# Board.net
KiCad netlist of a schematic drawn in EAGLE
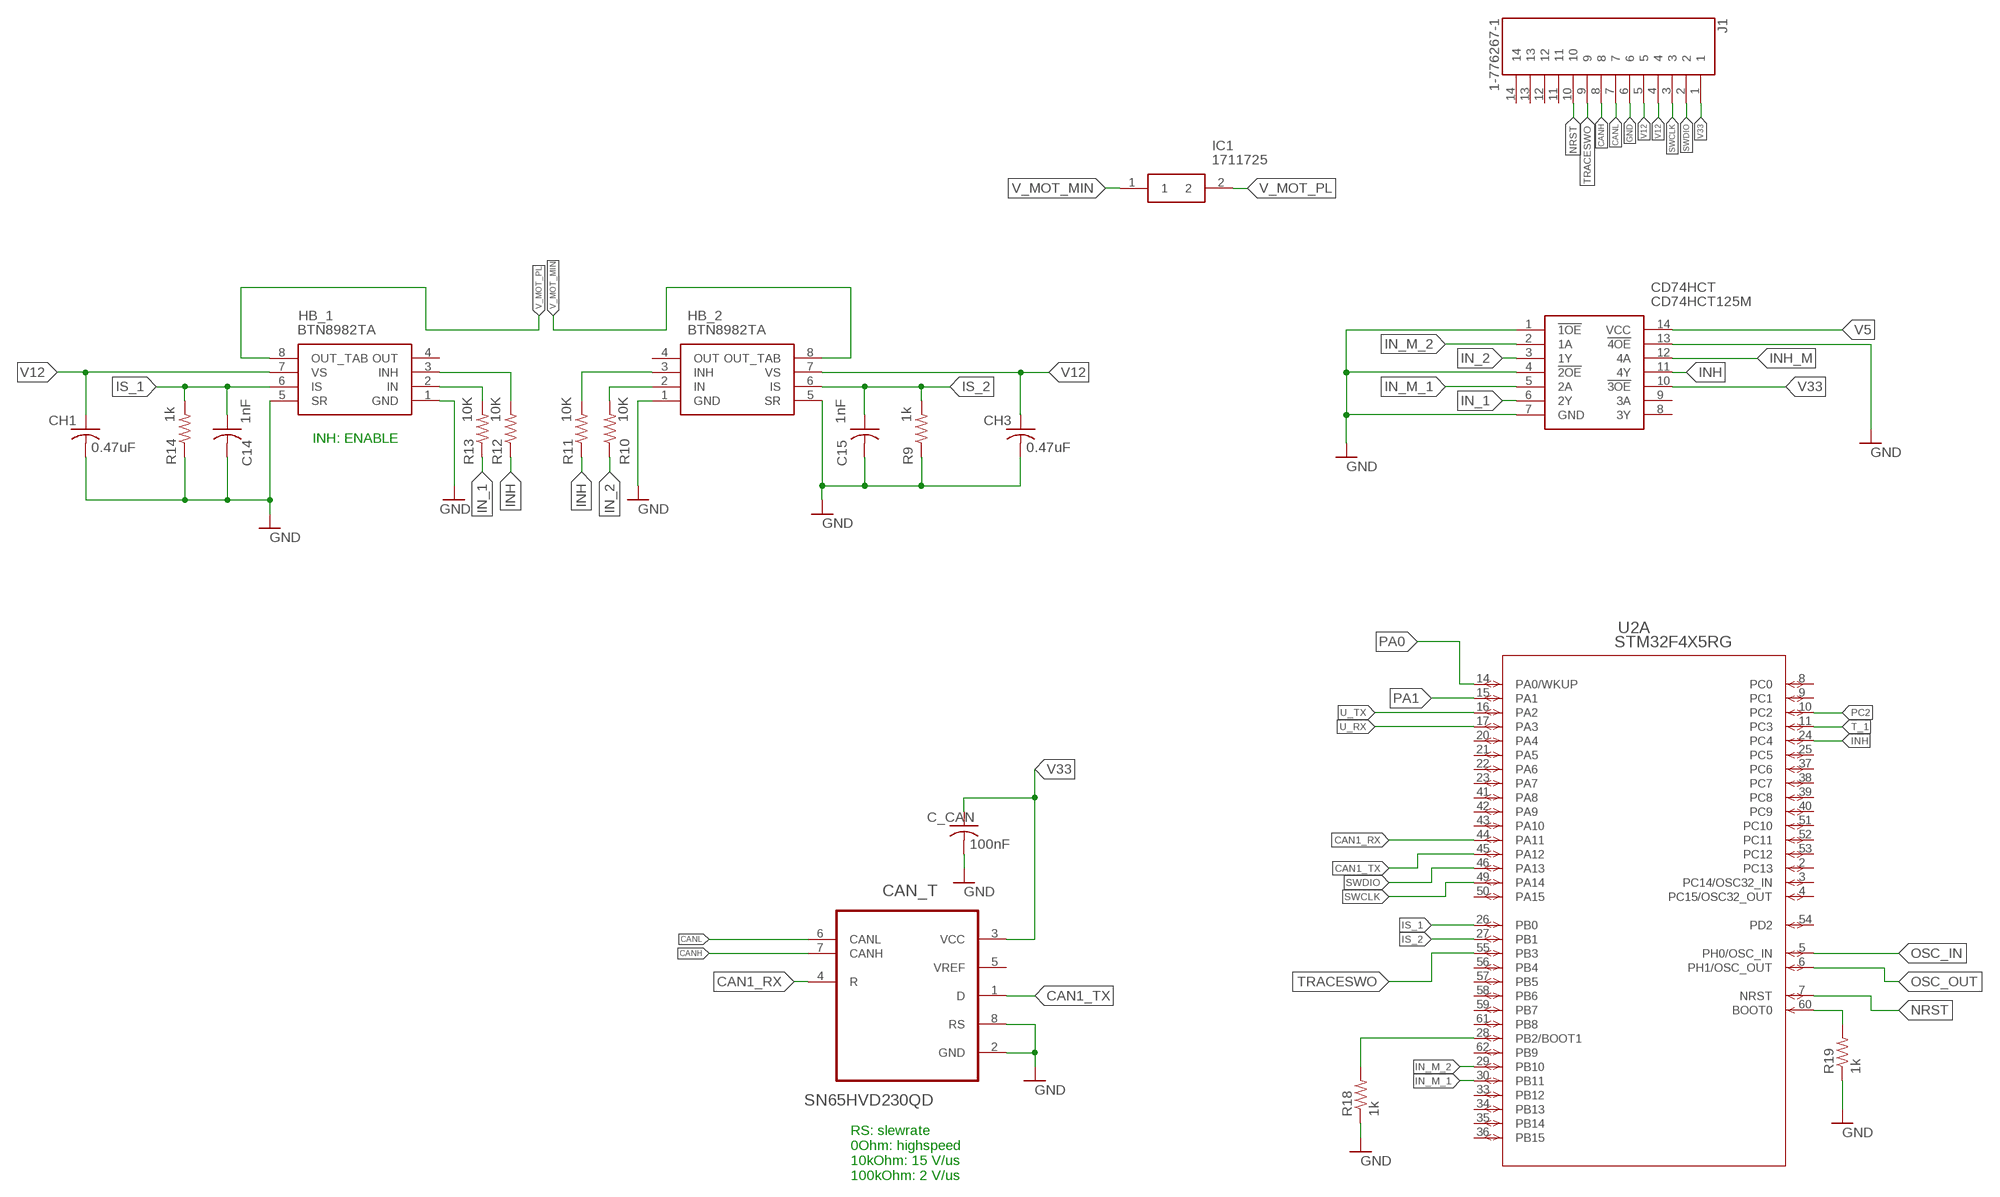
[diagram p0: schematic, sheet 1, part 1 of 2]
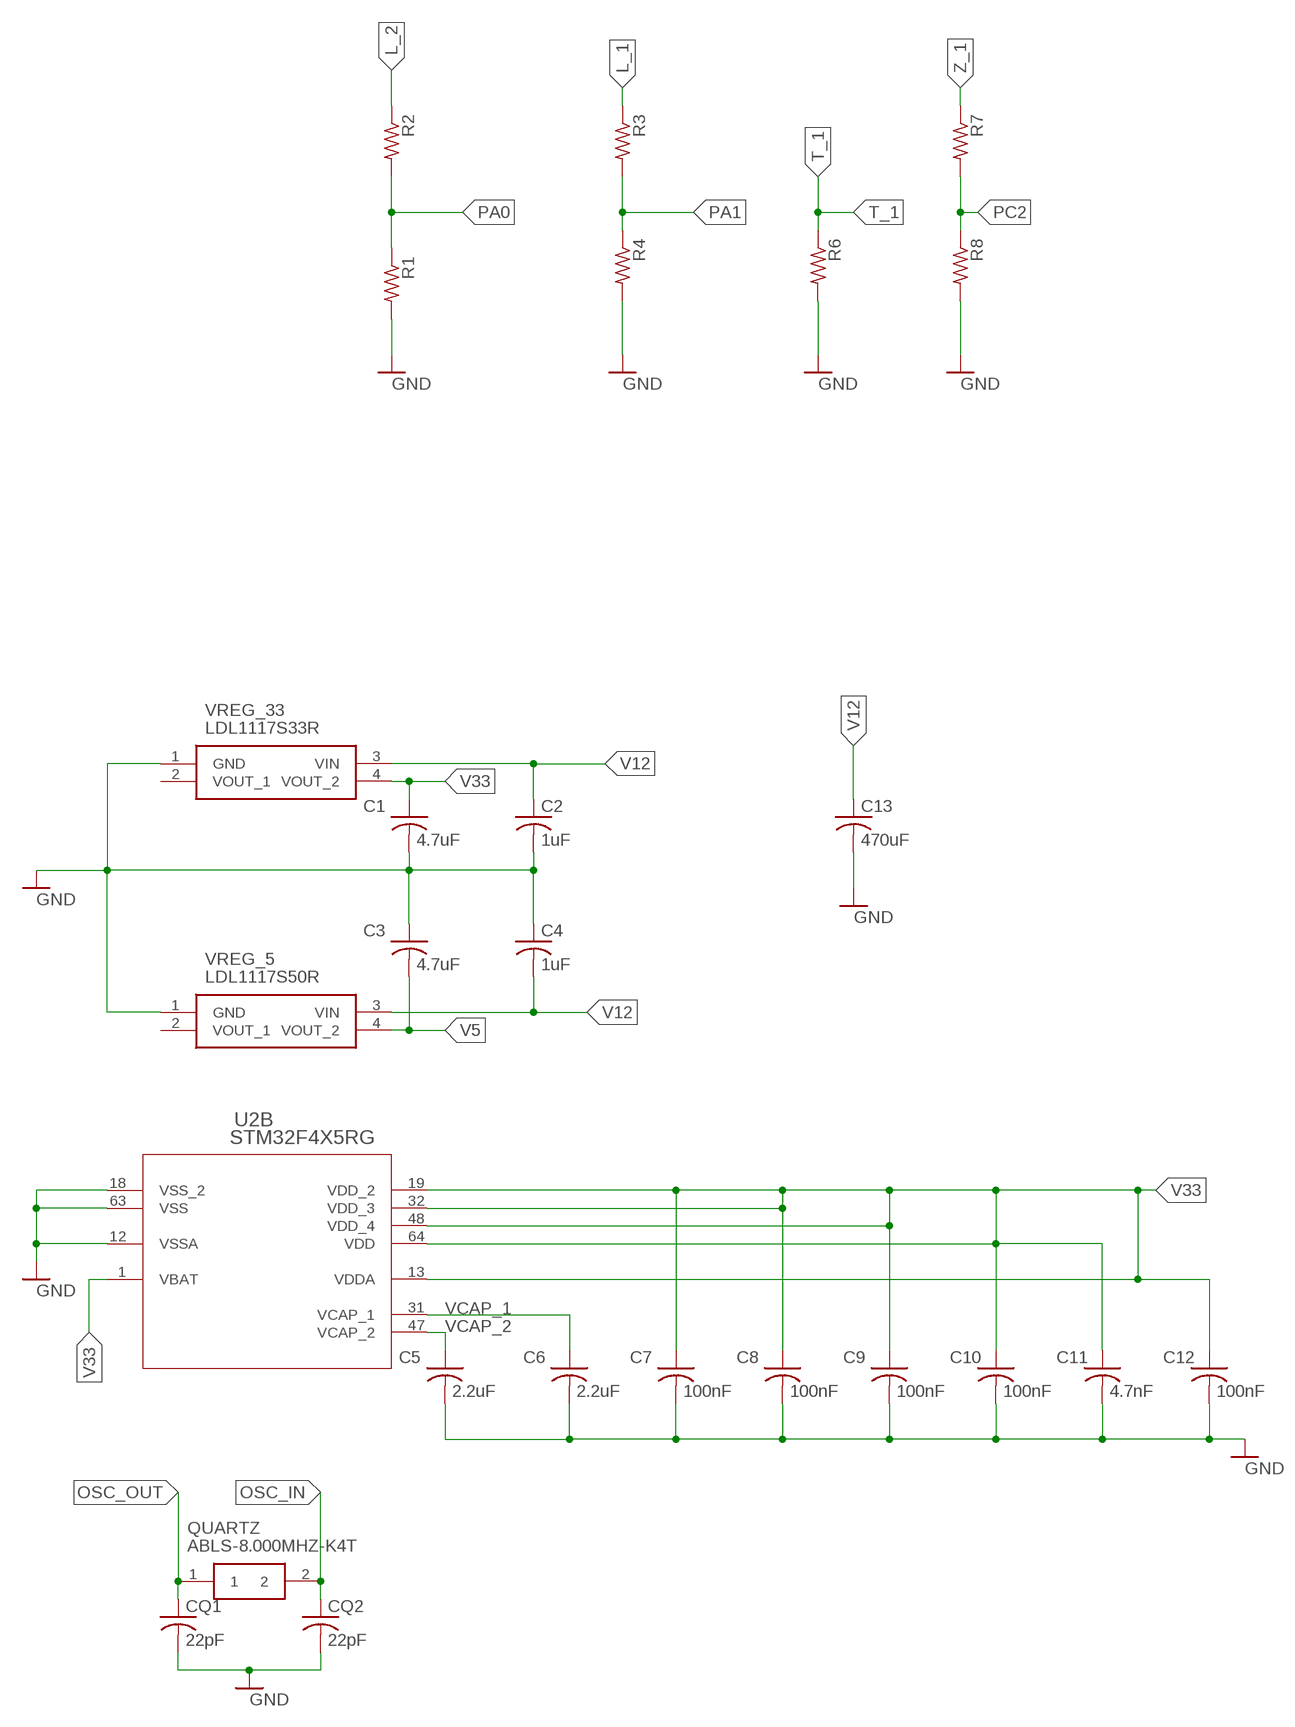
[diagram p1: schematic, sheet 1, part 2 of 2]

(export (version "E")
  (design (tool "Eeschema 10.0.6"))
  (components
    (comp (ref "C1")
      (value "4.7uF")
      (footprint "eagle-import:C1206")
      (libsource (lib "eagle-import") (part "C-USC1206"))
    )
    (comp (ref "C2")
      (value "1uF")
      (footprint "eagle-import:C1206")
      (libsource (lib "eagle-import") (part "C-USC1206"))
    )
    (comp (ref "C3")
      (value "4.7uF")
      (footprint "eagle-import:C1206")
      (libsource (lib "eagle-import") (part "C-USC1206"))
    )
    (comp (ref "C4")
      (value "1uF")
      (footprint "eagle-import:C1206")
      (libsource (lib "eagle-import") (part "C-USC1206"))
    )
    (comp (ref "C5")
      (value "2.2uF")
      (footprint "eagle-import:C1206")
      (libsource (lib "eagle-import") (part "C-USC1206"))
    )
    (comp (ref "C6")
      (value "2.2uF")
      (footprint "eagle-import:C1206")
      (libsource (lib "eagle-import") (part "C-USC1206"))
    )
    (comp (ref "C7")
      (value "100nF")
      (footprint "eagle-import:C1206")
      (libsource (lib "eagle-import") (part "C-USC1206"))
    )
    (comp (ref "C8")
      (value "100nF")
      (footprint "eagle-import:C1206")
      (libsource (lib "eagle-import") (part "C-USC1206"))
    )
    (comp (ref "C9")
      (value "100nF")
      (footprint "eagle-import:C1206")
      (libsource (lib "eagle-import") (part "C-USC1206"))
    )
    (comp (ref "C10")
      (value "100nF")
      (footprint "eagle-import:C1206")
      (libsource (lib "eagle-import") (part "C-USC1206"))
    )
    (comp (ref "C11")
      (value "4.7nF")
      (footprint "eagle-import:C1206")
      (libsource (lib "eagle-import") (part "C-USC1206"))
    )
    (comp (ref "C12")
      (value "100nF")
      (footprint "eagle-import:C1206")
      (libsource (lib "eagle-import") (part "C-USC1206"))
    )
    (comp (ref "C13")
      (value "470uF")
      (footprint "eagle-import:C050-075X075")
      (libsource (lib "eagle-import") (part "C-US050-075X075"))
    )
    (comp (ref "C14")
      (value "1nF")
      (footprint "eagle-import:C1206")
      (libsource (lib "eagle-import") (part "C-USC1206"))
    )
    (comp (ref "C15")
      (value "1nF")
      (footprint "eagle-import:C1206")
      (libsource (lib "eagle-import") (part "C-USC1206"))
    )
    (comp (ref "CAN_T")
      (value "SN65HVD230QD")
      (footprint "eagle-import:SOIC127P600X175-8N")
      (fields (field (name "MF") "TEXAS INSTRUMENTS") (field (name "MPN") "SN65HVD230QD.."))
      (libsource (lib "eagle-import") (part "SN65HVD230QD"))
    )
    (comp (ref "CD74HCT")
      (value "CD74HCT125M")
      (footprint "eagle-import:SOIC127P600X175-14N")
      (fields (field (name "MOUSER_PART_NUMBER") "595-CD74HCT125M"))
      (libsource (lib "eagle-import") (part "CD74HCT125M"))
    )
    (comp (ref "CH1")
      (value "0.47uF")
      (footprint "eagle-import:C1206")
      (libsource (lib "eagle-import") (part "C-USC1206"))
    )
    (comp (ref "CH3")
      (value "0.47uF")
      (footprint "eagle-import:C1206")
      (libsource (lib "eagle-import") (part "C-USC1206"))
    )
    (comp (ref "CQ1")
      (value "22pF")
      (footprint "eagle-import:C0805")
      (libsource (lib "eagle-import") (part "C-USC0805"))
    )
    (comp (ref "CQ2")
      (value "22pF")
      (footprint "eagle-import:C0805")
      (libsource (lib "eagle-import") (part "C-USC0805"))
    )
    (comp (ref "C_CAN")
      (value "100nF")
      (footprint "eagle-import:C1206")
      (libsource (lib "eagle-import") (part "C-USC1206"))
    )
    (comp (ref "HB_1")
      (value "BTN8982TA")
      (footprint "eagle-import:TO127P1500X440-8N")
      (fields (field (name "MOUSER_PART_NUMBER") "726-BTN8982TA"))
      (libsource (lib "eagle-import") (part "BTN8982TA"))
    )
    (comp (ref "HB_2")
      (value "BTN8982TA")
      (footprint "eagle-import:TO127P1500X440-8N")
      (fields (field (name "MOUSER_PART_NUMBER") "726-BTN8982TA"))
      (libsource (lib "eagle-import") (part "BTN8982TA"))
    )
    (comp (ref "IC1")
      (value "1711725")
      (footprint "eagle-import:PHEONIX-5.08PITCH-2PIN")
      (fields (field (name "MOUSER_PART_NUMBER") "651-1711725"))
      (libsource (lib "eagle-import") (part "1711725"))
    )
    (comp (ref "J1")
      (value "1-776267-1")
      (footprint "eagle-import:TE_1-776267-1")
      (fields (field (name "DIGI-KEY_PART_NUMBER") "A142413-ND") (field (name "MF") "TE Connectivity"))
      (libsource (lib "eagle-import") (part "1-776267-1"))
    )
    (comp (ref "QUARTZ")
      (value "ABLS-8.000MHZ-K4T")
      (footprint "eagle-import:ABLS-12.000MHZ-B2")
      (fields (field (name "MOUSER_PART_NUMBER") "815-ABLS-8.0MK4-T") (field (name "MF") "ABRACON"))
      (libsource (lib "eagle-import") (part "ABLS-8.000MHZ-K4T"))
    )
    (comp (ref "R1")
      (value "R-US_R1206")
      (footprint "eagle-import:R1206")
      (libsource (lib "eagle-import") (part "R-US_R1206"))
    )
    (comp (ref "R2")
      (value "R-US_R1206")
      (footprint "eagle-import:R1206")
      (libsource (lib "eagle-import") (part "R-US_R1206"))
    )
    (comp (ref "R3")
      (value "R-US_R1206")
      (footprint "eagle-import:R1206")
      (libsource (lib "eagle-import") (part "R-US_R1206"))
    )
    (comp (ref "R4")
      (value "R-US_R1206")
      (footprint "eagle-import:R1206")
      (libsource (lib "eagle-import") (part "R-US_R1206"))
    )
    (comp (ref "R6")
      (value "R-US_R1206")
      (footprint "eagle-import:R1206")
      (libsource (lib "eagle-import") (part "R-US_R1206"))
    )
    (comp (ref "R7")
      (value "R-US_R1206")
      (footprint "eagle-import:R1206")
      (libsource (lib "eagle-import") (part "R-US_R1206"))
    )
    (comp (ref "R8")
      (value "R-US_R1206")
      (footprint "eagle-import:R1206")
      (libsource (lib "eagle-import") (part "R-US_R1206"))
    )
    (comp (ref "R9")
      (value "1k")
      (footprint "eagle-import:R1206")
      (libsource (lib "eagle-import") (part "R-US_R1206"))
    )
    (comp (ref "R10")
      (value "10K")
      (footprint "eagle-import:R1206")
      (libsource (lib "eagle-import") (part "R-US_R1206"))
    )
    (comp (ref "R11")
      (value "10K")
      (footprint "eagle-import:R1206")
      (libsource (lib "eagle-import") (part "R-US_R1206"))
    )
    (comp (ref "R12")
      (value "10K")
      (footprint "eagle-import:R1206")
      (libsource (lib "eagle-import") (part "R-US_R1206"))
    )
    (comp (ref "R13")
      (value "10K")
      (footprint "eagle-import:R1206")
      (libsource (lib "eagle-import") (part "R-US_R1206"))
    )
    (comp (ref "R14")
      (value "1k")
      (footprint "eagle-import:R1206")
      (libsource (lib "eagle-import") (part "R-US_R1206"))
    )
    (comp (ref "R18")
      (value "1k")
      (footprint "eagle-import:R1206")
      (libsource (lib "eagle-import") (part "R-US_R1206"))
    )
    (comp (ref "R19")
      (value "1k")
      (footprint "eagle-import:R1206")
      (libsource (lib "eagle-import") (part "R-US_R1206"))
    )
    (comp (ref "U2")
      (value "STM32F4X5RG")
      (footprint "eagle-import:LQFP64-10X10MM")
      (fields (field (name "OC_FARNELL") "unknown"))
      (libsource (lib "eagle-import") (part "STM32F4X5RG"))
    )
    (comp (ref "VREG_5")
      (value "LDL1117S50R")
      (footprint "eagle-import:SOT230P700X180-4N")
      (fields (field (name "MOUSER_PART_NUMBER") "511-LDL1117S50R") (field (name "MF") "STMICROELECTRONICS"))
      (libsource (lib "eagle-import") (part "LDL1117S50R"))
    )
    (comp (ref "VREG_33")
      (value "LDL1117S33R")
      (footprint "eagle-import:SOT230P700X180-4N")
      (fields (field (name "MOUSER_PART_NUMBER") "511-LDL1117S33R") (field (name "MF") "STMICROELECTRONICS"))
      (libsource (lib "eagle-import") (part "LDL1117S33R"))
    )
  )
  (nets
    (net (code "1") (name "/VCAP_1") (class "Default")
      (node (ref "C6") (pin "1") (pinfunction "1_1") (pintype "passive"))
      (node (ref "U2") (pin "31") (pinfunction "VCAP_1_31") (pintype "power_in"))
    )
    (net (code "2") (name "/VCAP_2") (class "Default")
      (node (ref "C5") (pin "1") (pinfunction "1_1") (pintype "passive"))
      (node (ref "U2") (pin "47") (pinfunction "VCAP_2_47") (pintype "power_in"))
    )
    (net (code "3") (name "CAN1_RX") (class "Default")
      (node (ref "CAN_T") (pin "4") (pinfunction "R_4") (pintype "output"))
      (node (ref "U2") (pin "44") (pinfunction "PA11_44") (pintype "bidirectional"))
    )
    (net (code "4") (name "CAN1_TX") (class "Default")
      (node (ref "CAN_T") (pin "1") (pinfunction "D_1") (pintype "input"))
      (node (ref "U2") (pin "45") (pinfunction "PA12_45") (pintype "bidirectional"))
    )
    (net (code "5") (name "CANH") (class "Default")
      (node (ref "CAN_T") (pin "7") (pinfunction "CANH_7") (pintype "output"))
      (node (ref "J1") (pin "8") (pinfunction "8_8") (pintype "passive"))
    )
    (net (code "6") (name "CANL") (class "Default")
      (node (ref "CAN_T") (pin "6") (pinfunction "CANL_6") (pintype "output"))
      (node (ref "J1") (pin "7") (pinfunction "7_7") (pintype "passive"))
    )
    (net (code "7") (name "GND") (class "Default")
      (node (ref "C1") (pin "2") (pinfunction "2_2") (pintype "passive"))
      (node (ref "C10") (pin "2") (pinfunction "2_2") (pintype "passive"))
      (node (ref "C11") (pin "2") (pinfunction "2_2") (pintype "passive"))
      (node (ref "C12") (pin "2") (pinfunction "2_2") (pintype "passive"))
      (node (ref "C13") (pin "2") (pinfunction "2_2") (pintype "passive"))
      (node (ref "C14") (pin "2") (pinfunction "2_2") (pintype "passive"))
      (node (ref "C15") (pin "2") (pinfunction "2_2") (pintype "passive"))
      (node (ref "C2") (pin "2") (pinfunction "2_2") (pintype "passive"))
      (node (ref "C3") (pin "1") (pinfunction "1_1") (pintype "passive"))
      (node (ref "C4") (pin "1") (pinfunction "1_1") (pintype "passive"))
      (node (ref "C5") (pin "2") (pinfunction "2_2") (pintype "passive"))
      (node (ref "C6") (pin "2") (pinfunction "2_2") (pintype "passive"))
      (node (ref "C7") (pin "2") (pinfunction "2_2") (pintype "passive"))
      (node (ref "C8") (pin "2") (pinfunction "2_2") (pintype "passive"))
      (node (ref "C9") (pin "2") (pinfunction "2_2") (pintype "passive"))
      (node (ref "CAN_T") (pin "2") (pinfunction "GND_2") (pintype "passive"))
      (node (ref "CAN_T") (pin "8") (pinfunction "RS_8") (pintype "input"))
      (node (ref "CD74HCT") (pin "1") (pinfunction "~{1OE}_1") (pintype "bidirectional"))
      (node (ref "CD74HCT") (pin "13") (pinfunction "~{4OE}_13") (pintype "bidirectional"))
      (node (ref "CD74HCT") (pin "4") (pinfunction "~{2OE}_4") (pintype "bidirectional"))
      (node (ref "CD74HCT") (pin "7") (pinfunction "GND_7") (pintype "power_in"))
      (node (ref "CH1") (pin "2") (pinfunction "2_2") (pintype "passive"))
      (node (ref "CH3") (pin "2") (pinfunction "2_2") (pintype "passive"))
      (node (ref "CQ1") (pin "2") (pinfunction "2_2") (pintype "passive"))
      (node (ref "CQ2") (pin "2") (pinfunction "2_2") (pintype "passive"))
      (node (ref "C_CAN") (pin "2") (pinfunction "2_2") (pintype "passive"))
      (node (ref "HB_1") (pin "1") (pinfunction "GND_1") (pintype "power_in"))
      (node (ref "HB_1") (pin "5") (pinfunction "SR_5") (pintype "bidirectional"))
      (node (ref "HB_2") (pin "1") (pinfunction "GND_1") (pintype "power_in"))
      (node (ref "HB_2") (pin "5") (pinfunction "SR_5") (pintype "bidirectional"))
      (node (ref "J1") (pin "6") (pinfunction "6_6") (pintype "passive"))
      (node (ref "R1") (pin "2") (pinfunction "2_2") (pintype "passive"))
      (node (ref "R14") (pin "1") (pinfunction "1_1") (pintype "passive"))
      (node (ref "R18") (pin "1") (pinfunction "1_1") (pintype "passive"))
      (node (ref "R19") (pin "1") (pinfunction "1_1") (pintype "passive"))
      (node (ref "R4") (pin "2") (pinfunction "2_2") (pintype "passive"))
      (node (ref "R6") (pin "2") (pinfunction "2_2") (pintype "passive"))
      (node (ref "R8") (pin "2") (pinfunction "2_2") (pintype "passive"))
      (node (ref "R9") (pin "1") (pinfunction "1_1") (pintype "passive"))
      (node (ref "U2") (pin "12") (pinfunction "VSSA_12") (pintype "power_in"))
      (node (ref "U2") (pin "18") (pinfunction "VSS_2_18") (pintype "power_in"))
      (node (ref "U2") (pin "63") (pinfunction "VSS_63") (pintype "power_in"))
      (node (ref "VREG_33") (pin "1") (pinfunction "GND_1") (pintype "power_in"))
      (node (ref "VREG_5") (pin "1") (pinfunction "GND_1") (pintype "bidirectional"))
    )
    (net (code "8") (name "INH") (class "Default")
      (node (ref "CD74HCT") (pin "11") (pinfunction "4Y_11") (pintype "bidirectional"))
      (node (ref "R11") (pin "1") (pinfunction "1_1") (pintype "passive"))
      (node (ref "R12") (pin "1") (pinfunction "1_1") (pintype "passive"))
      (node (ref "U2") (pin "24") (pinfunction "PC4_24") (pintype "bidirectional"))
    )
    (net (code "9") (name "INH_M") (class "Default")
      (node (ref "CD74HCT") (pin "12") (pinfunction "4A_12") (pintype "bidirectional"))
    )
    (net (code "10") (name "IN_1") (class "Default")
      (node (ref "CD74HCT") (pin "6") (pinfunction "2Y_6") (pintype "bidirectional"))
      (node (ref "R13") (pin "1") (pinfunction "1_1") (pintype "passive"))
    )
    (net (code "11") (name "IN_2") (class "Default")
      (node (ref "CD74HCT") (pin "3") (pinfunction "1Y_3") (pintype "bidirectional"))
      (node (ref "R10") (pin "1") (pinfunction "1_1") (pintype "passive"))
    )
    (net (code "12") (name "IN_M_1") (class "Default")
      (node (ref "CD74HCT") (pin "5") (pinfunction "2A_5") (pintype "bidirectional"))
      (node (ref "U2") (pin "30") (pinfunction "PB11_30") (pintype "bidirectional"))
    )
    (net (code "13") (name "IN_M_2") (class "Default")
      (node (ref "CD74HCT") (pin "2") (pinfunction "1A_2") (pintype "bidirectional"))
      (node (ref "U2") (pin "29") (pinfunction "PB10_29") (pintype "bidirectional"))
    )
    (net (code "14") (name "IS_1") (class "Default")
      (node (ref "C14") (pin "1") (pinfunction "1_1") (pintype "passive"))
      (node (ref "HB_1") (pin "6") (pinfunction "IS_6") (pintype "bidirectional"))
      (node (ref "R14") (pin "2") (pinfunction "2_2") (pintype "passive"))
      (node (ref "U2") (pin "26") (pinfunction "PB0_26") (pintype "bidirectional"))
    )
    (net (code "15") (name "IS_2") (class "Default")
      (node (ref "C15") (pin "1") (pinfunction "1_1") (pintype "passive"))
      (node (ref "HB_2") (pin "6") (pinfunction "IS_6") (pintype "bidirectional"))
      (node (ref "R9") (pin "2") (pinfunction "2_2") (pintype "passive"))
      (node (ref "U2") (pin "27") (pinfunction "PB1_27") (pintype "bidirectional"))
    )
    (net (code "16") (name "L_1") (class "Default")
      (node (ref "R3") (pin "1") (pinfunction "1_1") (pintype "passive"))
    )
    (net (code "17") (name "L_2") (class "Default")
      (node (ref "R2") (pin "1") (pinfunction "1_1") (pintype "passive"))
    )
    (net (code "18") (name "NRST") (class "Default")
      (node (ref "J1") (pin "10") (pinfunction "10_10") (pintype "passive"))
      (node (ref "U2") (pin "7") (pinfunction "NRST_7") (pintype "bidirectional"))
    )
    (net (code "19") (name "Net-(HB_1-IN)") (class "Default")
      (node (ref "HB_1") (pin "2") (pinfunction "IN_2") (pintype "input"))
      (node (ref "R13") (pin "2") (pinfunction "2_2") (pintype "passive"))
    )
    (net (code "20") (name "Net-(HB_1-INH)") (class "Default")
      (node (ref "HB_1") (pin "3") (pinfunction "INH_3") (pintype "input"))
      (node (ref "R12") (pin "2") (pinfunction "2_2") (pintype "passive"))
    )
    (net (code "21") (name "Net-(HB_2-IN)") (class "Default")
      (node (ref "HB_2") (pin "2") (pinfunction "IN_2") (pintype "input"))
      (node (ref "R10") (pin "2") (pinfunction "2_2") (pintype "passive"))
    )
    (net (code "22") (name "Net-(HB_2-INH)") (class "Default")
      (node (ref "HB_2") (pin "3") (pinfunction "INH_3") (pintype "input"))
      (node (ref "R11") (pin "2") (pinfunction "2_2") (pintype "passive"))
    )
    (net (code "23") (name "Net-(U2A-BOOT0)") (class "Default")
      (node (ref "R19") (pin "2") (pinfunction "2_2") (pintype "passive"))
      (node (ref "U2") (pin "60") (pinfunction "BOOT0_60") (pintype "input"))
    )
    (net (code "24") (name "Net-(U2A-PB2{slash}BOOT1)") (class "Default")
      (node (ref "R18") (pin "2") (pinfunction "2_2") (pintype "passive"))
      (node (ref "U2") (pin "28") (pinfunction "PB2/BOOT1_28") (pintype "bidirectional"))
    )
    (net (code "25") (name "OSC_IN") (class "Default")
      (node (ref "CQ2") (pin "1") (pinfunction "1_1") (pintype "passive"))
      (node (ref "QUARTZ") (pin "2") (pinfunction "2_2") (pintype "bidirectional"))
      (node (ref "U2") (pin "5") (pinfunction "PH0/OSC_IN_5") (pintype "bidirectional"))
    )
    (net (code "26") (name "OSC_OUT") (class "Default")
      (node (ref "CQ1") (pin "1") (pinfunction "1_1") (pintype "passive"))
      (node (ref "QUARTZ") (pin "1") (pinfunction "1_1") (pintype "bidirectional"))
      (node (ref "U2") (pin "6") (pinfunction "PH1/OSC_OUT_6") (pintype "bidirectional"))
    )
    (net (code "27") (name "PA0") (class "Default")
      (node (ref "R1") (pin "1") (pinfunction "1_1") (pintype "passive"))
      (node (ref "R2") (pin "2") (pinfunction "2_2") (pintype "passive"))
      (node (ref "U2") (pin "14") (pinfunction "PA0/WKUP_14") (pintype "bidirectional"))
    )
    (net (code "28") (name "PA1") (class "Default")
      (node (ref "R3") (pin "2") (pinfunction "2_2") (pintype "passive"))
      (node (ref "R4") (pin "1") (pinfunction "1_1") (pintype "passive"))
      (node (ref "U2") (pin "15") (pinfunction "PA1_15") (pintype "bidirectional"))
    )
    (net (code "29") (name "PC2") (class "Default")
      (node (ref "R7") (pin "2") (pinfunction "2_2") (pintype "passive"))
      (node (ref "R8") (pin "1") (pinfunction "1_1") (pintype "passive"))
      (node (ref "U2") (pin "10") (pinfunction "PC2_10") (pintype "bidirectional"))
    )
    (net (code "30") (name "SWCLK") (class "Default")
      (node (ref "J1") (pin "3") (pinfunction "3_3") (pintype "passive"))
      (node (ref "U2") (pin "49") (pinfunction "PA14_49") (pintype "bidirectional"))
    )
    (net (code "31") (name "SWDIO") (class "Default")
      (node (ref "J1") (pin "2") (pinfunction "2_2") (pintype "passive"))
      (node (ref "U2") (pin "46") (pinfunction "PA13_46") (pintype "bidirectional"))
    )
    (net (code "32") (name "TRACESWO") (class "Default")
      (node (ref "J1") (pin "9") (pinfunction "9_9") (pintype "passive"))
      (node (ref "U2") (pin "55") (pinfunction "PB3_55") (pintype "bidirectional"))
    )
    (net (code "33") (name "T_1") (class "Default")
      (node (ref "R6") (pin "1") (pinfunction "1_1") (pintype "passive"))
      (node (ref "U2") (pin "11") (pinfunction "PC3_11") (pintype "bidirectional"))
    )
    (net (code "34") (name "U_RX") (class "Default")
      (node (ref "U2") (pin "17") (pinfunction "PA3_17") (pintype "bidirectional"))
    )
    (net (code "35") (name "U_TX") (class "Default")
      (node (ref "U2") (pin "16") (pinfunction "PA2_16") (pintype "bidirectional"))
    )
    (net (code "36") (name "V5") (class "Default")
      (node (ref "C3") (pin "2") (pinfunction "2_2") (pintype "passive"))
      (node (ref "CD74HCT") (pin "14") (pinfunction "VCC_14") (pintype "power_in"))
      (node (ref "VREG_5") (pin "4") (pinfunction "VOUT_2_4") (pintype "bidirectional"))
    )
    (net (code "37") (name "V12") (class "Default")
      (node (ref "C13") (pin "1") (pinfunction "1_1") (pintype "passive"))
      (node (ref "C2") (pin "1") (pinfunction "1_1") (pintype "passive"))
      (node (ref "C4") (pin "2") (pinfunction "2_2") (pintype "passive"))
      (node (ref "CH1") (pin "1") (pinfunction "1_1") (pintype "passive"))
      (node (ref "CH3") (pin "1") (pinfunction "1_1") (pintype "passive"))
      (node (ref "HB_1") (pin "7") (pinfunction "VS_7") (pintype "bidirectional"))
      (node (ref "HB_2") (pin "7") (pinfunction "VS_7") (pintype "bidirectional"))
      (node (ref "J1") (pin "4") (pinfunction "4_4") (pintype "passive"))
      (node (ref "J1") (pin "5") (pinfunction "5_5") (pintype "passive"))
      (node (ref "VREG_33") (pin "3") (pinfunction "VIN_3") (pintype "input"))
      (node (ref "VREG_5") (pin "3") (pinfunction "VIN_3") (pintype "bidirectional"))
    )
    (net (code "38") (name "V33") (class "Default")
      (node (ref "C1") (pin "1") (pinfunction "1_1") (pintype "passive"))
      (node (ref "C10") (pin "1") (pinfunction "1_1") (pintype "passive"))
      (node (ref "C11") (pin "1") (pinfunction "1_1") (pintype "passive"))
      (node (ref "C12") (pin "1") (pinfunction "1_1") (pintype "passive"))
      (node (ref "C7") (pin "1") (pinfunction "1_1") (pintype "passive"))
      (node (ref "C8") (pin "1") (pinfunction "1_1") (pintype "passive"))
      (node (ref "C9") (pin "1") (pinfunction "1_1") (pintype "passive"))
      (node (ref "CAN_T") (pin "3") (pinfunction "VCC_3") (pintype "power_in"))
      (node (ref "CD74HCT") (pin "10") (pinfunction "~{3OE}_10") (pintype "bidirectional"))
      (node (ref "C_CAN") (pin "1") (pinfunction "1_1") (pintype "passive"))
      (node (ref "J1") (pin "1") (pinfunction "1_1") (pintype "passive"))
      (node (ref "U2") (pin "1") (pinfunction "VBAT_1") (pintype "power_in"))
      (node (ref "U2") (pin "13") (pinfunction "VDDA_13") (pintype "power_in"))
      (node (ref "U2") (pin "19") (pinfunction "VDD_2_19") (pintype "power_in"))
      (node (ref "U2") (pin "32") (pinfunction "VDD_3_32") (pintype "power_in"))
      (node (ref "U2") (pin "48") (pinfunction "VDD_4_48") (pintype "power_in"))
      (node (ref "U2") (pin "64") (pinfunction "VDD_64") (pintype "power_in"))
      (node (ref "VREG_33") (pin "4") (pinfunction "VOUT_2_4") (pintype "output"))
    )
    (net (code "39") (name "V_MOT_MIN") (class "Default")
      (node (ref "HB_2") (pin "8") (pinfunction "OUT_TAB_8") (pintype "output"))
      (node (ref "IC1") (pin "1") (pinfunction "1_1") (pintype "bidirectional"))
    )
    (net (code "40") (name "V_MOT_PL") (class "Default")
      (node (ref "HB_1") (pin "8") (pinfunction "OUT_TAB_8") (pintype "output"))
      (node (ref "IC1") (pin "2") (pinfunction "2_2") (pintype "bidirectional"))
    )
    (net (code "41") (name "Z_1") (class "Default")
      (node (ref "R7") (pin "1") (pinfunction "1_1") (pintype "passive"))
    )
    (net (code "42") (name "unconnected-(CAN_T-VREF-Pad5)") (class "Default")
      (node (ref "CAN_T") (pin "5") (pinfunction "VREF_5") (pintype "input"))
    )
    (net (code "43") (name "unconnected-(CD74HCT-3A-Pad9)") (class "Default")
      (node (ref "CD74HCT") (pin "9") (pinfunction "3A_9") (pintype "bidirectional"))
    )
    (net (code "44") (name "unconnected-(CD74HCT-3Y-Pad8)") (class "Default")
      (node (ref "CD74HCT") (pin "8") (pinfunction "3Y_8") (pintype "bidirectional"))
    )
    (net (code "45") (name "unconnected-(HB_1-OUT-Pad4)") (class "Default")
      (node (ref "HB_1") (pin "4") (pinfunction "OUT_4") (pintype "output"))
    )
    (net (code "46") (name "unconnected-(HB_2-OUT-Pad4)") (class "Default")
      (node (ref "HB_2") (pin "4") (pinfunction "OUT_4") (pintype "output"))
    )
    (net (code "47") (name "unconnected-(J1-Pad11)") (class "Default")
      (node (ref "J1") (pin "11") (pinfunction "11_11") (pintype "passive"))
    )
    (net (code "48") (name "unconnected-(J1-Pad12)") (class "Default")
      (node (ref "J1") (pin "12") (pinfunction "12_12") (pintype "passive"))
    )
    (net (code "49") (name "unconnected-(J1-Pad13)") (class "Default")
      (node (ref "J1") (pin "13") (pinfunction "13_13") (pintype "passive"))
    )
    (net (code "50") (name "unconnected-(J1-Pad14)") (class "Default")
      (node (ref "J1") (pin "14") (pinfunction "14_14") (pintype "passive"))
    )
    (net (code "51") (name "unconnected-(U2A-PA4-Pad20)") (class "Default")
      (node (ref "U2") (pin "20") (pinfunction "PA4_20") (pintype "bidirectional"))
    )
    (net (code "52") (name "unconnected-(U2A-PA5-Pad21)") (class "Default")
      (node (ref "U2") (pin "21") (pinfunction "PA5_21") (pintype "bidirectional"))
    )
    (net (code "53") (name "unconnected-(U2A-PA6-Pad22)") (class "Default")
      (node (ref "U2") (pin "22") (pinfunction "PA6_22") (pintype "bidirectional"))
    )
    (net (code "54") (name "unconnected-(U2A-PA7-Pad23)") (class "Default")
      (node (ref "U2") (pin "23") (pinfunction "PA7_23") (pintype "bidirectional"))
    )
    (net (code "55") (name "unconnected-(U2A-PA8-Pad41)") (class "Default")
      (node (ref "U2") (pin "41") (pinfunction "PA8_41") (pintype "bidirectional"))
    )
    (net (code "56") (name "unconnected-(U2A-PA9-Pad42)") (class "Default")
      (node (ref "U2") (pin "42") (pinfunction "PA9_42") (pintype "bidirectional"))
    )
    (net (code "57") (name "unconnected-(U2A-PA10-Pad43)") (class "Default")
      (node (ref "U2") (pin "43") (pinfunction "PA10_43") (pintype "bidirectional"))
    )
    (net (code "58") (name "unconnected-(U2A-PA15-Pad50)") (class "Default")
      (node (ref "U2") (pin "50") (pinfunction "PA15_50") (pintype "bidirectional"))
    )
    (net (code "59") (name "unconnected-(U2A-PB4-Pad56)") (class "Default")
      (node (ref "U2") (pin "56") (pinfunction "PB4_56") (pintype "bidirectional"))
    )
    (net (code "60") (name "unconnected-(U2A-PB5-Pad57)") (class "Default")
      (node (ref "U2") (pin "57") (pinfunction "PB5_57") (pintype "bidirectional"))
    )
    (net (code "61") (name "unconnected-(U2A-PB6-Pad58)") (class "Default")
      (node (ref "U2") (pin "58") (pinfunction "PB6_58") (pintype "bidirectional"))
    )
    (net (code "62") (name "unconnected-(U2A-PB7-Pad59)") (class "Default")
      (node (ref "U2") (pin "59") (pinfunction "PB7_59") (pintype "bidirectional"))
    )
    (net (code "63") (name "unconnected-(U2A-PB8-Pad61)") (class "Default")
      (node (ref "U2") (pin "61") (pinfunction "PB8_61") (pintype "bidirectional"))
    )
    (net (code "64") (name "unconnected-(U2A-PB9-Pad62)") (class "Default")
      (node (ref "U2") (pin "62") (pinfunction "PB9_62") (pintype "bidirectional"))
    )
    (net (code "65") (name "unconnected-(U2A-PB12-Pad33)") (class "Default")
      (node (ref "U2") (pin "33") (pinfunction "PB12_33") (pintype "bidirectional"))
    )
    (net (code "66") (name "unconnected-(U2A-PB13-Pad34)") (class "Default")
      (node (ref "U2") (pin "34") (pinfunction "PB13_34") (pintype "bidirectional"))
    )
    (net (code "67") (name "unconnected-(U2A-PB14-Pad35)") (class "Default")
      (node (ref "U2") (pin "35") (pinfunction "PB14_35") (pintype "bidirectional"))
    )
    (net (code "68") (name "unconnected-(U2A-PB15-Pad36)") (class "Default")
      (node (ref "U2") (pin "36") (pinfunction "PB15_36") (pintype "bidirectional"))
    )
    (net (code "69") (name "unconnected-(U2A-PC0-Pad8)") (class "Default")
      (node (ref "U2") (pin "8") (pinfunction "PC0_8") (pintype "bidirectional"))
    )
    (net (code "70") (name "unconnected-(U2A-PC1-Pad9)") (class "Default")
      (node (ref "U2") (pin "9") (pinfunction "PC1_9") (pintype "bidirectional"))
    )
    (net (code "71") (name "unconnected-(U2A-PC5-Pad25)") (class "Default")
      (node (ref "U2") (pin "25") (pinfunction "PC5_25") (pintype "bidirectional"))
    )
    (net (code "72") (name "unconnected-(U2A-PC6-Pad37)") (class "Default")
      (node (ref "U2") (pin "37") (pinfunction "PC6_37") (pintype "bidirectional"))
    )
    (net (code "73") (name "unconnected-(U2A-PC7-Pad38)") (class "Default")
      (node (ref "U2") (pin "38") (pinfunction "PC7_38") (pintype "bidirectional"))
    )
    (net (code "74") (name "unconnected-(U2A-PC8-Pad39)") (class "Default")
      (node (ref "U2") (pin "39") (pinfunction "PC8_39") (pintype "bidirectional"))
    )
    (net (code "75") (name "unconnected-(U2A-PC9-Pad40)") (class "Default")
      (node (ref "U2") (pin "40") (pinfunction "PC9_40") (pintype "bidirectional"))
    )
    (net (code "76") (name "unconnected-(U2A-PC10-Pad51)") (class "Default")
      (node (ref "U2") (pin "51") (pinfunction "PC10_51") (pintype "bidirectional"))
    )
    (net (code "77") (name "unconnected-(U2A-PC11-Pad52)") (class "Default")
      (node (ref "U2") (pin "52") (pinfunction "PC11_52") (pintype "bidirectional"))
    )
    (net (code "78") (name "unconnected-(U2A-PC12-Pad53)") (class "Default")
      (node (ref "U2") (pin "53") (pinfunction "PC12_53") (pintype "bidirectional"))
    )
    (net (code "79") (name "unconnected-(U2A-PC13-Pad2)") (class "Default")
      (node (ref "U2") (pin "2") (pinfunction "PC13_2") (pintype "bidirectional"))
    )
    (net (code "80") (name "unconnected-(U2A-PC14{slash}OSC32_IN-Pad3)") (class "Default")
      (node (ref "U2") (pin "3") (pinfunction "PC14/OSC32_IN_3") (pintype "bidirectional"))
    )
    (net (code "81") (name "unconnected-(U2A-PC15{slash}OSC32_OUT-Pad4)") (class "Default")
      (node (ref "U2") (pin "4") (pinfunction "PC15/OSC32_OUT_4") (pintype "bidirectional"))
    )
    (net (code "82") (name "unconnected-(U2A-PD2-Pad54)") (class "Default")
      (node (ref "U2") (pin "54") (pinfunction "PD2_54") (pintype "bidirectional"))
    )
    (net (code "83") (name "unconnected-(VREG_5-VOUT_1-Pad2)") (class "Default")
      (node (ref "VREG_5") (pin "2") (pinfunction "VOUT_1_2") (pintype "bidirectional"))
    )
    (net (code "84") (name "unconnected-(VREG_33-VOUT_1-Pad2)") (class "Default")
      (node (ref "VREG_33") (pin "2") (pinfunction "VOUT_1_2") (pintype "output"))
    )
  )
)
